# ethernet_poe.net
KiCad netlist of a schematic drawn in EAGLE
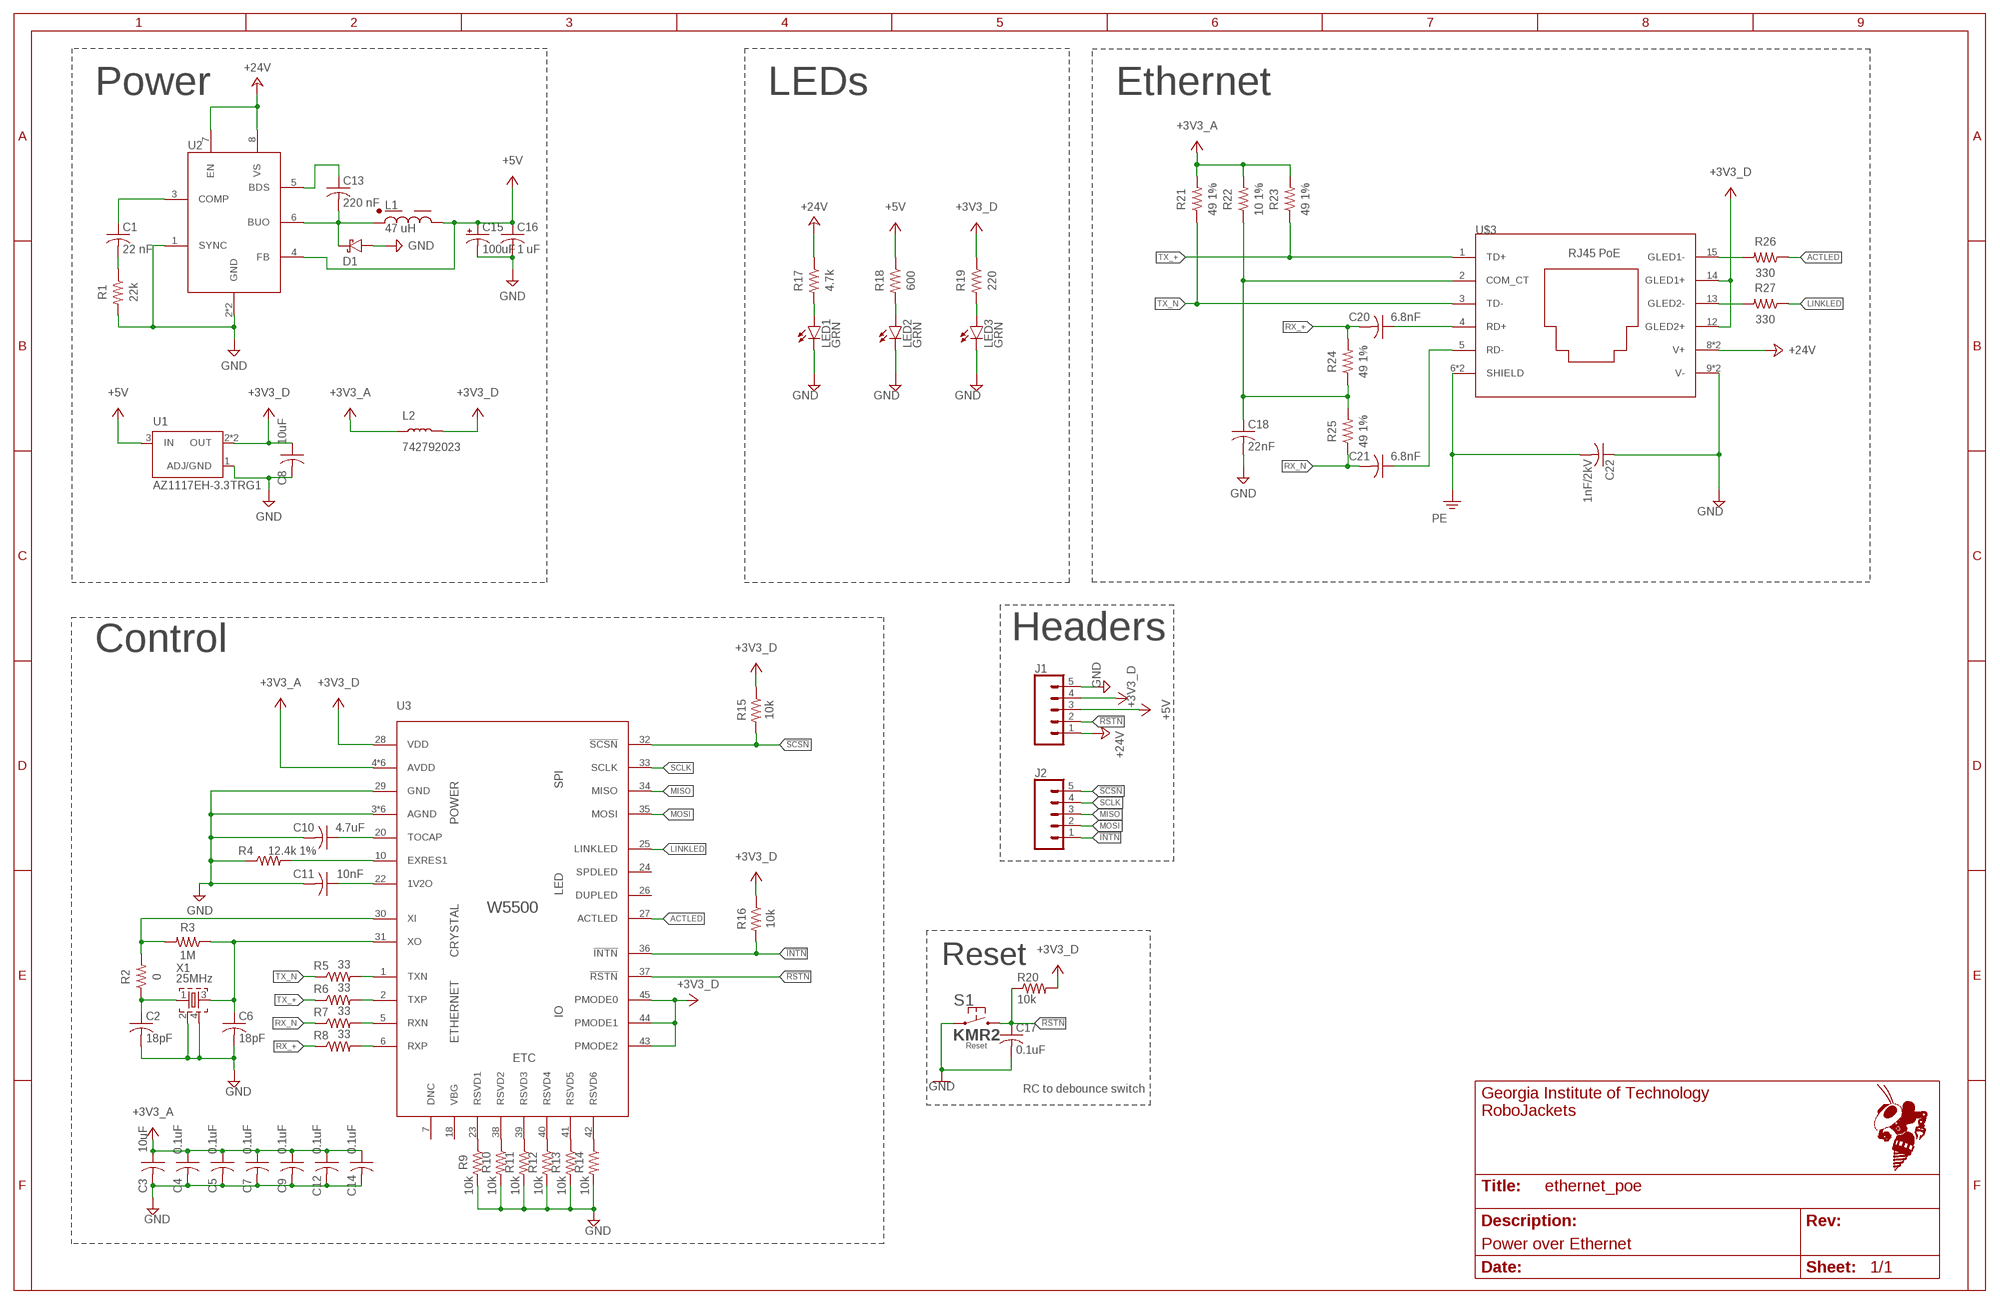
[diagram p0: schematic, sheet 1]

(export (version "E")
  (design (tool "Eeschema 10.0.6"))
  (components
    (comp (ref "C1")
      (value "22 nF")
      (footprint "eagle-import:C0603")
      (libsource (lib "eagle-import") (part "C-USC0603"))
    )
    (comp (ref "C2")
      (value "18pF")
      (footprint "eagle-import:C0603")
      (libsource (lib "eagle-import") (part "C-USC0603"))
    )
    (comp (ref "C3")
      (value "10uF")
      (footprint "eagle-import:C0603")
      (libsource (lib "eagle-import") (part "C-USC0603"))
    )
    (comp (ref "C4")
      (value "0.1uF")
      (footprint "eagle-import:C0603")
      (libsource (lib "eagle-import") (part "C-USC0603"))
    )
    (comp (ref "C5")
      (value "0.1uF")
      (footprint "eagle-import:C0603")
      (libsource (lib "eagle-import") (part "C-USC0603"))
    )
    (comp (ref "C6")
      (value "18pF")
      (footprint "eagle-import:C0603")
      (libsource (lib "eagle-import") (part "C-USC0603"))
    )
    (comp (ref "C7")
      (value "0.1uF")
      (footprint "eagle-import:C0603")
      (libsource (lib "eagle-import") (part "C-USC0603"))
    )
    (comp (ref "C8")
      (value "10uF")
      (footprint "eagle-import:C0603")
      (libsource (lib "eagle-import") (part "C-USC0603"))
    )
    (comp (ref "C9")
      (value "0.1uF")
      (footprint "eagle-import:C0603")
      (libsource (lib "eagle-import") (part "C-USC0603"))
    )
    (comp (ref "C10")
      (value "4.7uF")
      (footprint "eagle-import:C0603")
      (libsource (lib "eagle-import") (part "C-USC0603"))
    )
    (comp (ref "C11")
      (value "10nF")
      (footprint "eagle-import:C0603")
      (libsource (lib "eagle-import") (part "C-USC0603"))
    )
    (comp (ref "C12")
      (value "0.1uF")
      (footprint "eagle-import:C0603")
      (libsource (lib "eagle-import") (part "C-USC0603"))
    )
    (comp (ref "C13")
      (value "220 nF")
      (footprint "eagle-import:C0603")
      (libsource (lib "eagle-import") (part "C-USC0603"))
    )
    (comp (ref "C14")
      (value "0.1uF")
      (footprint "eagle-import:C0603")
      (libsource (lib "eagle-import") (part "C-USC0603"))
    )
    (comp (ref "C15")
      (value "100uF")
      (footprint "eagle-import:E2-5")
      (libsource (lib "eagle-import") (part "CPOL-USE2-5"))
    )
    (comp (ref "C16")
      (value "1 uF")
      (footprint "eagle-import:C0603")
      (libsource (lib "eagle-import") (part "C-USC0603"))
    )
    (comp (ref "C17")
      (value "0.1uF")
      (footprint "eagle-import:C0603")
      (libsource (lib "eagle-import") (part "C-USC0603"))
    )
    (comp (ref "C18")
      (value "22nF")
      (footprint "eagle-import:C0603")
      (libsource (lib "eagle-import") (part "C-USC0603"))
    )
    (comp (ref "C20")
      (value "6.8nF")
      (footprint "eagle-import:C0603")
      (libsource (lib "eagle-import") (part "C-USC0603"))
    )
    (comp (ref "C21")
      (value "6.8nF")
      (footprint "eagle-import:C0603")
      (libsource (lib "eagle-import") (part "C-USC0603"))
    )
    (comp (ref "C22")
      (value "1nF/2kV")
      (footprint "eagle-import:C1206")
      (libsource (lib "eagle-import") (part "C-USC1206"))
    )
    (comp (ref "D1")
      (value "SCHOTTKYSOD-323")
      (footprint "eagle-import:SOD-323")
      (libsource (lib "eagle-import") (part "SCHOTTKYSOD-323"))
    )
    (comp (ref "J1")
      (value "CONN_05")
      (footprint "eagle-import:1X05")
      (libsource (lib "eagle-import") (part "CONN_05"))
    )
    (comp (ref "J2")
      (value "CONN_05")
      (footprint "eagle-import:1X05")
      (libsource (lib "eagle-import") (part "CONN_05"))
    )
    (comp (ref "L1")
      (value "47 uH")
      (footprint "eagle-import:744771147")
      (libsource (lib "eagle-import") (part "744771147"))
    )
    (comp (ref "L2")
      (value "742792023")
      (footprint "eagle-import:0805")
      (libsource (lib "eagle-import") (part "INDUCTOR_0805"))
    )
    (comp (ref "LED1")
      (value "GRN")
      (footprint "eagle-import:CHIP-LED0603")
      (libsource (lib "eagle-import") (part "LEDCHIP-LED0603"))
    )
    (comp (ref "LED2")
      (value "GRN")
      (footprint "eagle-import:CHIP-LED0603")
      (libsource (lib "eagle-import") (part "LEDCHIP-LED0603"))
    )
    (comp (ref "LED3")
      (value "GRN")
      (footprint "eagle-import:CHIP-LED0603")
      (libsource (lib "eagle-import") (part "LEDCHIP-LED0603"))
    )
    (comp (ref "R1")
      (value "22k")
      (footprint "eagle-import:R0603")
      (libsource (lib "eagle-import") (part "R-US_R0603"))
    )
    (comp (ref "R2")
      (value "0")
      (footprint "eagle-import:R0603")
      (libsource (lib "eagle-import") (part "R-US_R0603"))
    )
    (comp (ref "R3")
      (value "1M")
      (footprint "eagle-import:R0603")
      (libsource (lib "eagle-import") (part "R-US_R0603"))
    )
    (comp (ref "R4")
      (value "12.4k 1%")
      (footprint "eagle-import:R0603")
      (libsource (lib "eagle-import") (part "R-US_R0603"))
    )
    (comp (ref "R5")
      (value "33")
      (footprint "eagle-import:R0603")
      (libsource (lib "eagle-import") (part "R-US_R0603"))
    )
    (comp (ref "R6")
      (value "33")
      (footprint "eagle-import:R0603")
      (libsource (lib "eagle-import") (part "R-US_R0603"))
    )
    (comp (ref "R7")
      (value "33")
      (footprint "eagle-import:R0603")
      (libsource (lib "eagle-import") (part "R-US_R0603"))
    )
    (comp (ref "R8")
      (value "33")
      (footprint "eagle-import:R0603")
      (libsource (lib "eagle-import") (part "R-US_R0603"))
    )
    (comp (ref "R9")
      (value "10k")
      (footprint "eagle-import:R0603")
      (libsource (lib "eagle-import") (part "R-US_R0603"))
    )
    (comp (ref "R10")
      (value "10k")
      (footprint "eagle-import:R0603")
      (libsource (lib "eagle-import") (part "R-US_R0603"))
    )
    (comp (ref "R11")
      (value "10k")
      (footprint "eagle-import:R0603")
      (libsource (lib "eagle-import") (part "R-US_R0603"))
    )
    (comp (ref "R12")
      (value "10k")
      (footprint "eagle-import:R0603")
      (libsource (lib "eagle-import") (part "R-US_R0603"))
    )
    (comp (ref "R13")
      (value "10k")
      (footprint "eagle-import:R0603")
      (libsource (lib "eagle-import") (part "R-US_R0603"))
    )
    (comp (ref "R14")
      (value "10k")
      (footprint "eagle-import:R0603")
      (libsource (lib "eagle-import") (part "R-US_R0603"))
    )
    (comp (ref "R15")
      (value "10k")
      (footprint "eagle-import:R0603")
      (libsource (lib "eagle-import") (part "R-US_R0603"))
    )
    (comp (ref "R16")
      (value "10k")
      (footprint "eagle-import:R0603")
      (libsource (lib "eagle-import") (part "R-US_R0603"))
    )
    (comp (ref "R17")
      (value "4.7k")
      (footprint "eagle-import:R0603")
      (libsource (lib "eagle-import") (part "R-US_R0603"))
    )
    (comp (ref "R18")
      (value "600")
      (footprint "eagle-import:R0603")
      (libsource (lib "eagle-import") (part "R-US_R0603"))
    )
    (comp (ref "R19")
      (value "220")
      (footprint "eagle-import:R0603")
      (libsource (lib "eagle-import") (part "R-US_R0603"))
    )
    (comp (ref "R20")
      (value "10k")
      (footprint "eagle-import:R0603")
      (libsource (lib "eagle-import") (part "R-US_R0603"))
    )
    (comp (ref "R21")
      (value "49 1%")
      (footprint "eagle-import:R0603")
      (libsource (lib "eagle-import") (part "R-US_R0603"))
    )
    (comp (ref "R22")
      (value "10 1%")
      (footprint "eagle-import:R0603")
      (libsource (lib "eagle-import") (part "R-US_R0603"))
    )
    (comp (ref "R23")
      (value "49 1%")
      (footprint "eagle-import:R0603")
      (libsource (lib "eagle-import") (part "R-US_R0603"))
    )
    (comp (ref "R24")
      (value "49 1%")
      (footprint "eagle-import:R0603")
      (libsource (lib "eagle-import") (part "R-US_R0603"))
    )
    (comp (ref "R25")
      (value "49 1%")
      (footprint "eagle-import:R0603")
      (libsource (lib "eagle-import") (part "R-US_R0603"))
    )
    (comp (ref "R26")
      (value "330")
      (footprint "eagle-import:R0603")
      (libsource (lib "eagle-import") (part "R-US_R0603"))
    )
    (comp (ref "R27")
      (value "330")
      (footprint "eagle-import:R0603")
      (libsource (lib "eagle-import") (part "R-US_R0603"))
    )
    (comp (ref "S1")
      (value "KMR2")
      (footprint "eagle-import:KMR2")
      (fields (field (name "FUNCTION") "Reset"))
      (libsource (lib "eagle-import") (part "KMR2"))
    )
    (comp (ref "U$3")
      (value "SI-52003-F")
      (footprint "eagle-import:SI-52003-F")
      (libsource (lib "eagle-import") (part "SI-52003-F"))
    )
    (comp (ref "U1")
      (value "AZ1117EH-3.3TRG1")
      (footprint "eagle-import:SOT230P700X180-4N")
      (libsource (lib "eagle-import") (part "AZ1117EH-3.3TRG1"))
    )
    (comp (ref "U2")
      (value "IFX91041")
      (footprint "eagle-import:SOIC-8-EXPOSED_PAD")
      (libsource (lib "eagle-import") (part "IFX91041"))
    )
    (comp (ref "U3")
      (value "W5500")
      (footprint "eagle-import:48-LQFP")
      (libsource (lib "eagle-import") (part "W5500"))
    )
    (comp (ref "X1")
      (value "25MHz")
      (footprint "eagle-import:OSCILLATOR-SMD-2.5X2")
      (libsource (lib "eagle-import") (part "ABM10W-25.0000MHZ-6-K1Z-T3"))
    )
  )
  (nets
    (net (code "1") (name "+3V3_A") (class "Default")
      (node (ref "C12") (pin "1") (pinfunction "1_1") (pintype "passive"))
      (node (ref "C14") (pin "1") (pinfunction "1_1") (pintype "passive"))
      (node (ref "C3") (pin "1") (pinfunction "1_1") (pintype "passive"))
      (node (ref "C4") (pin "1") (pinfunction "1_1") (pintype "passive"))
      (node (ref "C5") (pin "1") (pinfunction "1_1") (pintype "passive"))
      (node (ref "C7") (pin "1") (pinfunction "1_1") (pintype "passive"))
      (node (ref "C9") (pin "1") (pinfunction "1_1") (pintype "passive"))
      (node (ref "L2") (pin "1") (pinfunction "1_1") (pintype "passive"))
      (node (ref "R21") (pin "2") (pinfunction "2_2") (pintype "passive"))
      (node (ref "R22") (pin "2") (pinfunction "2_2") (pintype "passive"))
      (node (ref "R23") (pin "2") (pinfunction "2_2") (pintype "passive"))
      (node (ref "U3") (pin "11") (pinfunction "AVDD_11") (pintype "power_in"))
      (node (ref "U3") (pin "15") (pinfunction "AVDD_15") (pintype "power_in"))
      (node (ref "U3") (pin "17") (pinfunction "AVDD_17") (pintype "power_in"))
      (node (ref "U3") (pin "21") (pinfunction "AVDD_21") (pintype "power_in"))
      (node (ref "U3") (pin "4") (pinfunction "AVDD_4") (pintype "power_in"))
      (node (ref "U3") (pin "8") (pinfunction "AVDD_8") (pintype "power_in"))
    )
    (net (code "2") (name "+3V3_D") (class "Default")
      (node (ref "C8") (pin "1") (pinfunction "1_1") (pintype "passive"))
      (node (ref "J1") (pin "4") (pinfunction "4_4") (pintype "passive"))
      (node (ref "L2") (pin "2") (pinfunction "2_2") (pintype "passive"))
      (node (ref "R15") (pin "1") (pinfunction "1_1") (pintype "passive"))
      (node (ref "R16") (pin "1") (pinfunction "1_1") (pintype "passive"))
      (node (ref "R19") (pin "1") (pinfunction "1_1") (pintype "passive"))
      (node (ref "R20") (pin "2") (pinfunction "2_2") (pintype "passive"))
      (node (ref "U$3") (pin "12") (pinfunction "GLED2+_12") (pintype "bidirectional"))
      (node (ref "U$3") (pin "14") (pinfunction "GLED1+_14") (pintype "bidirectional"))
      (node (ref "U1") (pin "2") (pinfunction "OUT_2") (pintype "output"))
      (node (ref "U1") (pin "4") (pinfunction "OUT_4") (pintype "output"))
      (node (ref "U3") (pin "28") (pinfunction "VDD_28") (pintype "power_in"))
      (node (ref "U3") (pin "43") (pinfunction "PMODE2_43") (pintype "input"))
      (node (ref "U3") (pin "44") (pinfunction "PMODE1_44") (pintype "input"))
      (node (ref "U3") (pin "45") (pinfunction "PMODE0_45") (pintype "input"))
    )
    (net (code "3") (name "+5V") (class "Default")
      (node (ref "C15") (pin "+") (pinfunction "+_+") (pintype "passive"))
      (node (ref "C16") (pin "1") (pinfunction "1_1") (pintype "passive"))
      (node (ref "J1") (pin "3") (pinfunction "3_3") (pintype "passive"))
      (node (ref "L1") (pin "1") (pinfunction "P$1_1") (pintype "passive"))
      (node (ref "R18") (pin "1") (pinfunction "1_1") (pintype "passive"))
      (node (ref "U1") (pin "3") (pinfunction "IN_3") (pintype "input"))
      (node (ref "U2") (pin "4") (pinfunction "FB_4") (pintype "bidirectional"))
    )
    (net (code "4") (name "+24V") (class "Default")
      (node (ref "J1") (pin "1") (pinfunction "1_1") (pintype "passive"))
      (node (ref "R17") (pin "1") (pinfunction "1_1") (pintype "passive"))
      (node (ref "U$3") (pin "10") (pinfunction "V+_10") (pintype "bidirectional"))
      (node (ref "U$3") (pin "8") (pinfunction "V+_8") (pintype "bidirectional"))
      (node (ref "U2") (pin "7") (pinfunction "EN_7") (pintype "input"))
      (node (ref "U2") (pin "8") (pinfunction "VS_8") (pintype "power_in"))
    )
    (net (code "5") (name "/~{INTN}") (class "Default")
      (node (ref "J2") (pin "1") (pinfunction "1_1") (pintype "passive"))
      (node (ref "R16") (pin "2") (pinfunction "2_2") (pintype "passive"))
      (node (ref "U3") (pin "36") (pinfunction "~{INTN}_36") (pintype "output"))
    )
    (net (code "6") (name "/~{RSTN}") (class "Default")
      (node (ref "C17") (pin "1") (pinfunction "1_1") (pintype "passive"))
      (node (ref "J1") (pin "2") (pinfunction "2_2") (pintype "passive"))
      (node (ref "R20") (pin "1") (pinfunction "1_1") (pintype "passive"))
      (node (ref "S1") (pin "2.1") (pinfunction "2_2.1") (pintype "passive"))
      (node (ref "S1") (pin "2.2") (pinfunction "2_2.2") (pintype "passive"))
      (node (ref "U3") (pin "37") (pinfunction "~{RSTN}_37") (pintype "input"))
    )
    (net (code "7") (name "/~{SCSN}") (class "Default")
      (node (ref "J2") (pin "5") (pinfunction "5_5") (pintype "passive"))
      (node (ref "R15") (pin "2") (pinfunction "2_2") (pintype "passive"))
      (node (ref "U3") (pin "32") (pinfunction "~{SCSN}_32") (pintype "input"))
    )
    (net (code "8") (name "ACTLED") (class "Default")
      (node (ref "R26") (pin "1") (pinfunction "1_1") (pintype "passive"))
      (node (ref "U3") (pin "27") (pinfunction "ACTLED_27") (pintype "output"))
    )
    (net (code "9") (name "GND") (class "Default")
      (node (ref "C10") (pin "2") (pinfunction "2_2") (pintype "passive"))
      (node (ref "C11") (pin "2") (pinfunction "2_2") (pintype "passive"))
      (node (ref "C12") (pin "2") (pinfunction "2_2") (pintype "passive"))
      (node (ref "C14") (pin "2") (pinfunction "2_2") (pintype "passive"))
      (node (ref "C15") (pin "-") (pinfunction "-_-") (pintype "passive"))
      (node (ref "C16") (pin "2") (pinfunction "2_2") (pintype "passive"))
      (node (ref "C17") (pin "2") (pinfunction "2_2") (pintype "passive"))
      (node (ref "C18") (pin "2") (pinfunction "2_2") (pintype "passive"))
      (node (ref "C2") (pin "2") (pinfunction "2_2") (pintype "passive"))
      (node (ref "C22") (pin "1") (pinfunction "1_1") (pintype "passive"))
      (node (ref "C3") (pin "2") (pinfunction "2_2") (pintype "passive"))
      (node (ref "C4") (pin "2") (pinfunction "2_2") (pintype "passive"))
      (node (ref "C5") (pin "2") (pinfunction "2_2") (pintype "passive"))
      (node (ref "C6") (pin "2") (pinfunction "2_2") (pintype "passive"))
      (node (ref "C7") (pin "2") (pinfunction "2_2") (pintype "passive"))
      (node (ref "C8") (pin "2") (pinfunction "2_2") (pintype "passive"))
      (node (ref "C9") (pin "2") (pinfunction "2_2") (pintype "passive"))
      (node (ref "D1") (pin "A") (pinfunction "A_A") (pintype "passive"))
      (node (ref "J1") (pin "5") (pinfunction "5_5") (pintype "passive"))
      (node (ref "LED1") (pin "C") (pinfunction "C_C") (pintype "passive"))
      (node (ref "LED2") (pin "C") (pinfunction "C_C") (pintype "passive"))
      (node (ref "LED3") (pin "C") (pinfunction "C_C") (pintype "passive"))
      (node (ref "R1") (pin "2") (pinfunction "2_2") (pintype "passive"))
      (node (ref "R10") (pin "2") (pinfunction "2_2") (pintype "passive"))
      (node (ref "R11") (pin "2") (pinfunction "2_2") (pintype "passive"))
      (node (ref "R12") (pin "2") (pinfunction "2_2") (pintype "passive"))
      (node (ref "R13") (pin "2") (pinfunction "2_2") (pintype "passive"))
      (node (ref "R14") (pin "2") (pinfunction "2_2") (pintype "passive"))
      (node (ref "R4") (pin "1") (pinfunction "1_1") (pintype "passive"))
      (node (ref "R9") (pin "2") (pinfunction "2_2") (pintype "passive"))
      (node (ref "S1") (pin "1.1") (pinfunction "1_1.1") (pintype "passive"))
      (node (ref "S1") (pin "1.2") (pinfunction "1_1.2") (pintype "passive"))
      (node (ref "U$3") (pin "11") (pinfunction "V-_11") (pintype "bidirectional"))
      (node (ref "U$3") (pin "9") (pinfunction "V-_9") (pintype "bidirectional"))
      (node (ref "U1") (pin "1") (pinfunction "ADJ/GND_1") (pintype "power_in"))
      (node (ref "U2") (pin "1") (pinfunction "SYNC_1") (pintype "input"))
      (node (ref "U2") (pin "2") (pinfunction "GND_2") (pintype "power_in"))
      (node (ref "U2") (pin "P$9") (pinfunction "GND_P$9") (pintype "power_in"))
      (node (ref "U3") (pin "14") (pinfunction "AGND_14") (pintype "power_in"))
      (node (ref "U3") (pin "16") (pinfunction "AGND_16") (pintype "power_in"))
      (node (ref "U3") (pin "19") (pinfunction "AGND_19") (pintype "power_in"))
      (node (ref "U3") (pin "29") (pinfunction "GND_29") (pintype "power_in"))
      (node (ref "U3") (pin "3") (pinfunction "AGND_3") (pintype "power_in"))
      (node (ref "U3") (pin "48") (pinfunction "AGND_48") (pintype "power_in"))
      (node (ref "U3") (pin "9") (pinfunction "AGND_9") (pintype "power_in"))
      (node (ref "X1") (pin "2") (pinfunction "SHD1_2") (pintype "passive"))
      (node (ref "X1") (pin "4") (pinfunction "SHD2_4") (pintype "passive"))
    )
    (net (code "10") (name "LINKLED") (class "Default")
      (node (ref "R27") (pin "1") (pinfunction "1_1") (pintype "passive"))
      (node (ref "U3") (pin "25") (pinfunction "LINKLED_25") (pintype "output"))
    )
    (net (code "11") (name "MISO") (class "Default")
      (node (ref "J2") (pin "3") (pinfunction "3_3") (pintype "passive"))
      (node (ref "U3") (pin "34") (pinfunction "MISO_34") (pintype "output"))
    )
    (net (code "12") (name "MOSI") (class "Default")
      (node (ref "J2") (pin "2") (pinfunction "2_2") (pintype "passive"))
      (node (ref "U3") (pin "35") (pinfunction "MOSI_35") (pintype "input"))
    )
    (net (code "13") (name "Net-(C1-Pad2)") (class "Default")
      (node (ref "C1") (pin "2") (pinfunction "2_2") (pintype "passive"))
      (node (ref "R1") (pin "1") (pinfunction "1_1") (pintype "passive"))
    )
    (net (code "14") (name "Net-(LED1-PadA)") (class "Default")
      (node (ref "LED1") (pin "A") (pinfunction "A_A") (pintype "passive"))
      (node (ref "R17") (pin "2") (pinfunction "2_2") (pintype "passive"))
    )
    (net (code "15") (name "Net-(LED2-PadA)") (class "Default")
      (node (ref "LED2") (pin "A") (pinfunction "A_A") (pintype "passive"))
      (node (ref "R18") (pin "2") (pinfunction "2_2") (pintype "passive"))
    )
    (net (code "16") (name "Net-(LED3-PadA)") (class "Default")
      (node (ref "LED3") (pin "A") (pinfunction "A_A") (pintype "passive"))
      (node (ref "R19") (pin "2") (pinfunction "2_2") (pintype "passive"))
    )
    (net (code "17") (name "Net-(U$3-COM_CT)") (class "Default")
      (node (ref "C18") (pin "1") (pinfunction "1_1") (pintype "passive"))
      (node (ref "R22") (pin "1") (pinfunction "1_1") (pintype "passive"))
      (node (ref "R24") (pin "1") (pinfunction "1_1") (pintype "passive"))
      (node (ref "R25") (pin "2") (pinfunction "2_2") (pintype "passive"))
      (node (ref "U$3") (pin "2") (pinfunction "COM_CT_2") (pintype "bidirectional"))
    )
    (net (code "18") (name "Net-(U$3-GLED1-)") (class "Default")
      (node (ref "R26") (pin "2") (pinfunction "2_2") (pintype "passive"))
      (node (ref "U$3") (pin "15") (pinfunction "GLED1-_15") (pintype "bidirectional"))
    )
    (net (code "19") (name "Net-(U$3-GLED2-)") (class "Default")
      (node (ref "R27") (pin "2") (pinfunction "2_2") (pintype "passive"))
      (node (ref "U$3") (pin "13") (pinfunction "GLED2-_13") (pintype "bidirectional"))
    )
    (net (code "20") (name "Net-(U$3-RD+)") (class "Default")
      (node (ref "C20") (pin "1") (pinfunction "1_1") (pintype "passive"))
      (node (ref "U$3") (pin "4") (pinfunction "RD+_4") (pintype "bidirectional"))
    )
    (net (code "21") (name "Net-(U$3-RD-)") (class "Default")
      (node (ref "C21") (pin "1") (pinfunction "1_1") (pintype "passive"))
      (node (ref "U$3") (pin "5") (pinfunction "RD-_5") (pintype "bidirectional"))
    )
    (net (code "22") (name "Net-(U2-BDS)") (class "Default")
      (node (ref "C13") (pin "1") (pinfunction "1_1") (pintype "passive"))
      (node (ref "U2") (pin "5") (pinfunction "BDS_5") (pintype "bidirectional"))
    )
    (net (code "23") (name "Net-(U2-BUO)") (class "Default")
      (node (ref "C13") (pin "2") (pinfunction "2_2") (pintype "passive"))
      (node (ref "D1") (pin "C") (pinfunction "C_C") (pintype "passive"))
      (node (ref "L1") (pin "P$2") (pinfunction "P$2_P$2") (pintype "passive"))
      (node (ref "U2") (pin "6") (pinfunction "BUO_6") (pintype "bidirectional"))
    )
    (net (code "24") (name "Net-(U2-COMP)") (class "Default")
      (node (ref "C1") (pin "1") (pinfunction "1_1") (pintype "passive"))
      (node (ref "U2") (pin "3") (pinfunction "COMP_3") (pintype "bidirectional"))
    )
    (net (code "25") (name "Net-(U3-1V2O)") (class "Default")
      (node (ref "C11") (pin "1") (pinfunction "1_1") (pintype "passive"))
      (node (ref "U3") (pin "22") (pinfunction "1V2O_22") (pintype "output"))
    )
    (net (code "26") (name "Net-(U3-EXRES1)") (class "Default")
      (node (ref "R4") (pin "2") (pinfunction "2_2") (pintype "passive"))
      (node (ref "U3") (pin "10") (pinfunction "EXRES1_10") (pintype "output"))
    )
    (net (code "27") (name "Net-(U3-RSVD1)") (class "Default")
      (node (ref "R9") (pin "1") (pinfunction "1_1") (pintype "passive"))
      (node (ref "U3") (pin "23") (pinfunction "RSVD1_23") (pintype "input"))
    )
    (net (code "28") (name "Net-(U3-RSVD2)") (class "Default")
      (node (ref "R10") (pin "1") (pinfunction "1_1") (pintype "passive"))
      (node (ref "U3") (pin "38") (pinfunction "RSVD2_38") (pintype "input"))
    )
    (net (code "29") (name "Net-(U3-RSVD3)") (class "Default")
      (node (ref "R11") (pin "1") (pinfunction "1_1") (pintype "passive"))
      (node (ref "U3") (pin "39") (pinfunction "RSVD3_39") (pintype "input"))
    )
    (net (code "30") (name "Net-(U3-RSVD4)") (class "Default")
      (node (ref "R12") (pin "1") (pinfunction "1_1") (pintype "passive"))
      (node (ref "U3") (pin "40") (pinfunction "RSVD4_40") (pintype "input"))
    )
    (net (code "31") (name "Net-(U3-RSVD5)") (class "Default")
      (node (ref "R13") (pin "1") (pinfunction "1_1") (pintype "passive"))
      (node (ref "U3") (pin "41") (pinfunction "RSVD5_41") (pintype "input"))
    )
    (net (code "32") (name "Net-(U3-RSVD6)") (class "Default")
      (node (ref "R14") (pin "1") (pinfunction "1_1") (pintype "passive"))
      (node (ref "U3") (pin "42") (pinfunction "RSVD6_42") (pintype "input"))
    )
    (net (code "33") (name "Net-(U3-RXN)") (class "Default")
      (node (ref "R7") (pin "2") (pinfunction "2_2") (pintype "passive"))
      (node (ref "U3") (pin "5") (pinfunction "RXN_5") (pintype "input"))
    )
    (net (code "34") (name "Net-(U3-RXP)") (class "Default")
      (node (ref "R8") (pin "2") (pinfunction "2_2") (pintype "passive"))
      (node (ref "U3") (pin "6") (pinfunction "RXP_6") (pintype "input"))
    )
    (net (code "35") (name "Net-(U3-TOCAP)") (class "Default")
      (node (ref "C10") (pin "1") (pinfunction "1_1") (pintype "passive"))
      (node (ref "U3") (pin "20") (pinfunction "TOCAP_20") (pintype "output"))
    )
    (net (code "36") (name "Net-(U3-TXN)") (class "Default")
      (node (ref "R5") (pin "2") (pinfunction "2_2") (pintype "passive"))
      (node (ref "U3") (pin "1") (pinfunction "TXN_1") (pintype "output"))
    )
    (net (code "37") (name "Net-(U3-TXP)") (class "Default")
      (node (ref "R6") (pin "2") (pinfunction "2_2") (pintype "passive"))
      (node (ref "U3") (pin "2") (pinfunction "TXP_2") (pintype "output"))
    )
    (net (code "38") (name "Net-(U3-XI)") (class "Default")
      (node (ref "R2") (pin "2") (pinfunction "2_2") (pintype "passive"))
      (node (ref "R3") (pin "2") (pinfunction "2_2") (pintype "passive"))
      (node (ref "U3") (pin "30") (pinfunction "XI_30") (pintype "bidirectional"))
    )
    (net (code "39") (name "Net-(U3-XO)") (class "Default")
      (node (ref "C6") (pin "1") (pinfunction "1_1") (pintype "passive"))
      (node (ref "R3") (pin "1") (pinfunction "1_1") (pintype "passive"))
      (node (ref "U3") (pin "31") (pinfunction "XO_31") (pintype "bidirectional"))
      (node (ref "X1") (pin "3") (pinfunction "OUT_3") (pintype "passive"))
    )
    (net (code "40") (name "Net-(X1-IN)") (class "Default")
      (node (ref "C2") (pin "1") (pinfunction "1_1") (pintype "passive"))
      (node (ref "R2") (pin "1") (pinfunction "1_1") (pintype "passive"))
      (node (ref "X1") (pin "1") (pinfunction "IN_1") (pintype "passive"))
    )
    (net (code "41") (name "PE") (class "Default")
      (node (ref "C22") (pin "2") (pinfunction "2_2") (pintype "passive"))
      (node (ref "U$3") (pin "6") (pinfunction "SHIELD_6") (pintype "bidirectional"))
      (node (ref "U$3") (pin "7") (pinfunction "SHIELD_7") (pintype "bidirectional"))
    )
    (net (code "42") (name "RX_+") (class "Default")
      (node (ref "C20") (pin "2") (pinfunction "2_2") (pintype "passive"))
      (node (ref "R24") (pin "2") (pinfunction "2_2") (pintype "passive"))
      (node (ref "R8") (pin "1") (pinfunction "1_1") (pintype "passive"))
    )
    (net (code "43") (name "RX_N") (class "Default")
      (node (ref "C21") (pin "2") (pinfunction "2_2") (pintype "passive"))
      (node (ref "R25") (pin "1") (pinfunction "1_1") (pintype "passive"))
      (node (ref "R7") (pin "1") (pinfunction "1_1") (pintype "passive"))
    )
    (net (code "44") (name "SCLK") (class "Default")
      (node (ref "J2") (pin "4") (pinfunction "4_4") (pintype "passive"))
      (node (ref "U3") (pin "33") (pinfunction "SCLK_33") (pintype "input"))
    )
    (net (code "45") (name "TX_+") (class "Default")
      (node (ref "R23") (pin "1") (pinfunction "1_1") (pintype "passive"))
      (node (ref "R6") (pin "1") (pinfunction "1_1") (pintype "passive"))
      (node (ref "U$3") (pin "1") (pinfunction "TD+_1") (pintype "bidirectional"))
    )
    (net (code "46") (name "TX_N") (class "Default")
      (node (ref "R21") (pin "1") (pinfunction "1_1") (pintype "passive"))
      (node (ref "R5") (pin "1") (pinfunction "1_1") (pintype "passive"))
      (node (ref "U$3") (pin "3") (pinfunction "TD-_3") (pintype "bidirectional"))
    )
    (net (code "47") (name "unconnected-(U3-DNC-Pad7)") (class "Default")
      (node (ref "U3") (pin "7") (pinfunction "DNC_7") (pintype "no_connect"))
    )
    (net (code "48") (name "unconnected-(U3-DUPLED-Pad26)") (class "Default")
      (node (ref "U3") (pin "26") (pinfunction "DUPLED_26") (pintype "output"))
    )
    (net (code "49") (name "unconnected-(U3-SPDLED-Pad24)") (class "Default")
      (node (ref "U3") (pin "24") (pinfunction "SPDLED_24") (pintype "output"))
    )
    (net (code "50") (name "unconnected-(U3-VBG-Pad18)") (class "Default")
      (node (ref "U3") (pin "18") (pinfunction "VBG_18") (pintype "no_connect"))
    )
  )
)
